# M3_80.net
KiCad netlist of a schematic drawn in EAGLE
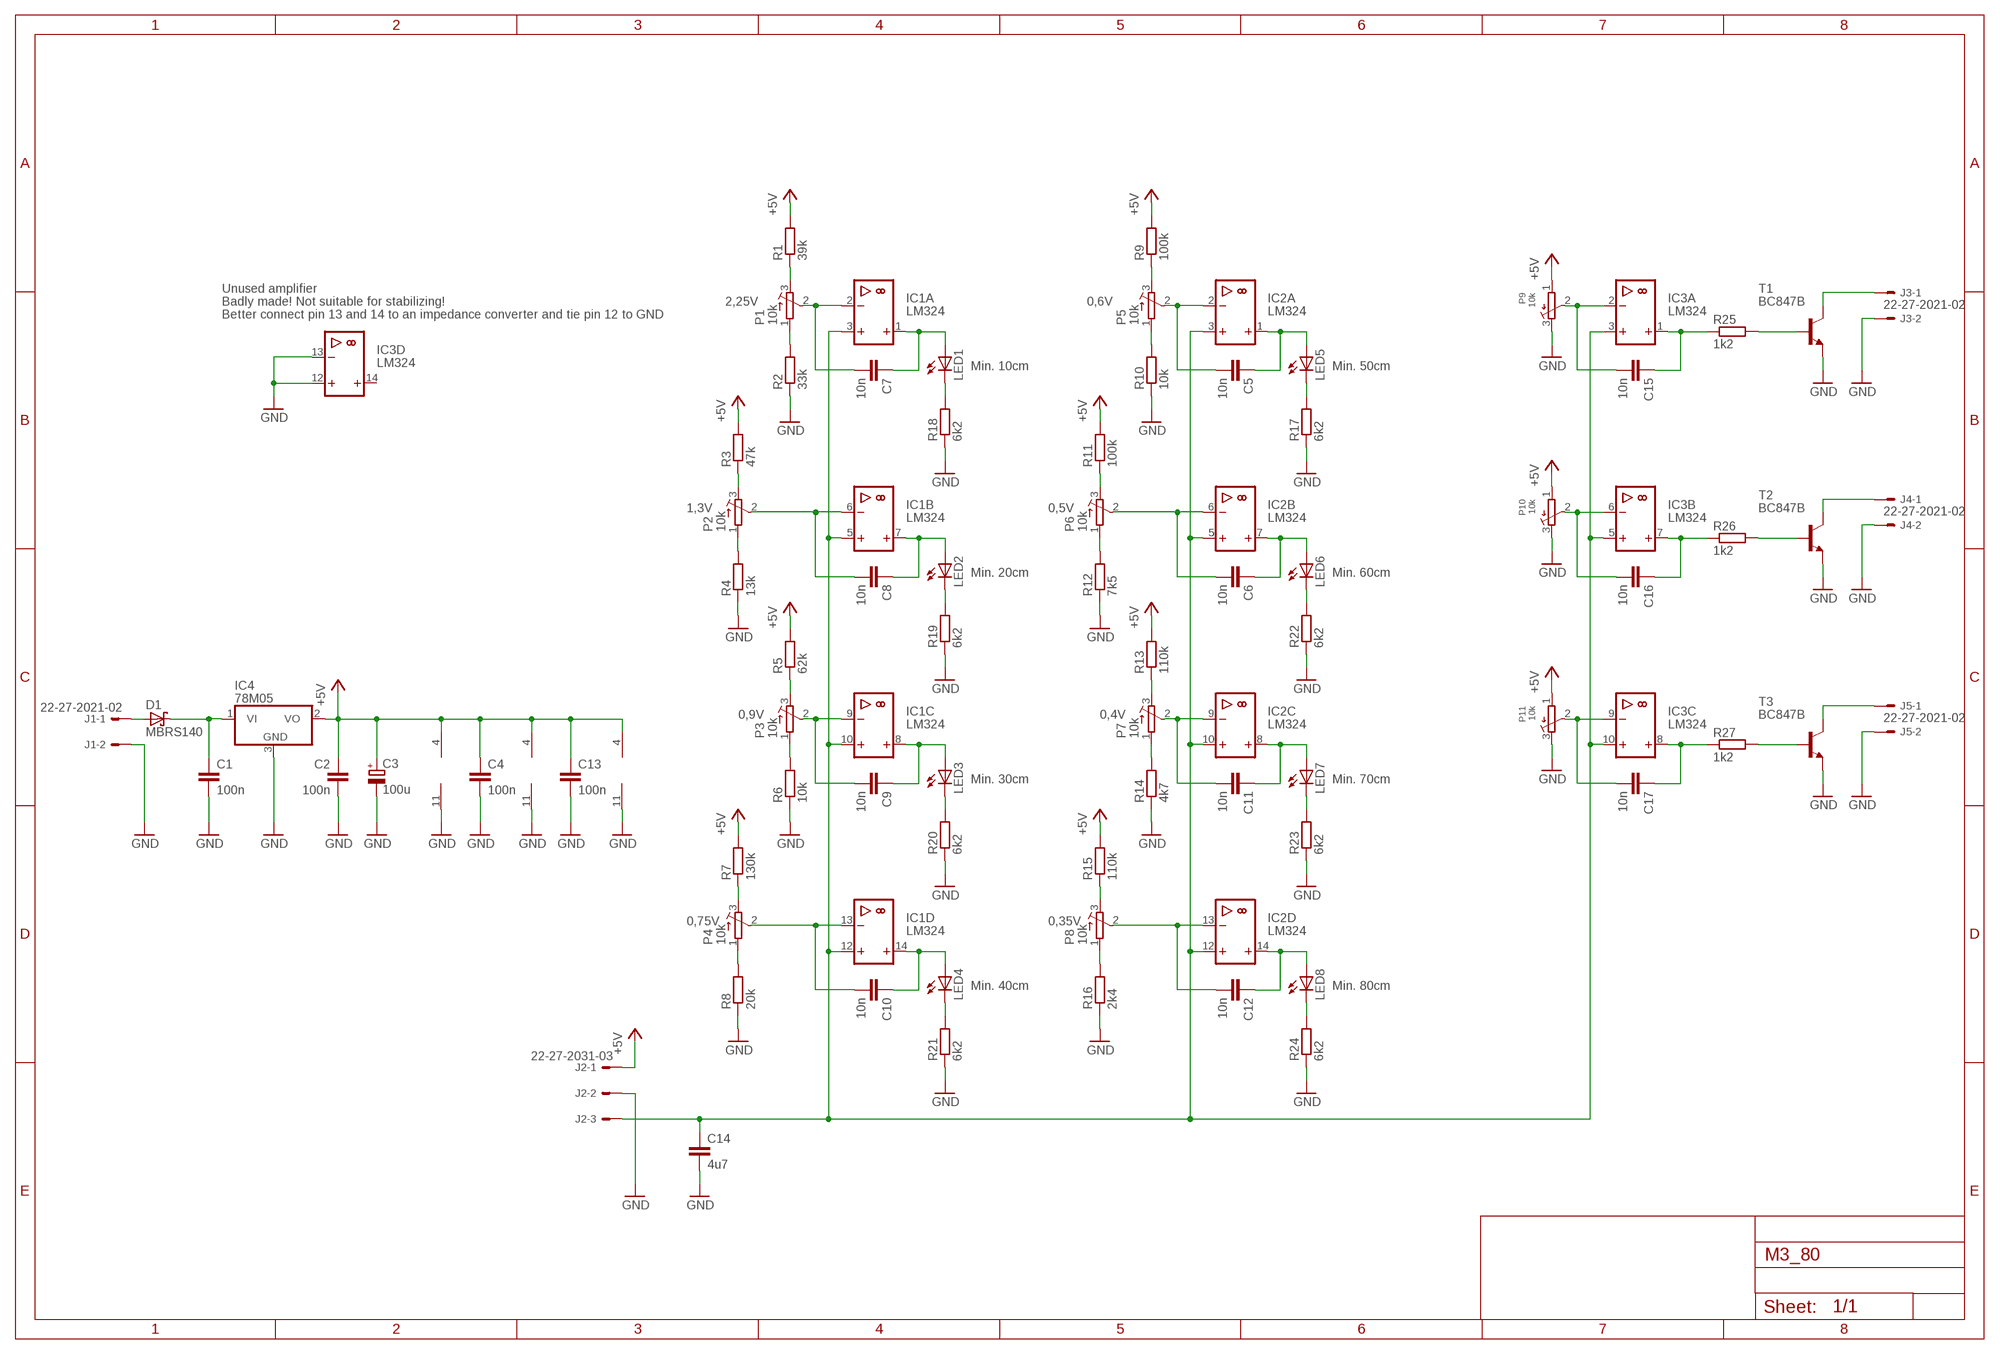
[diagram p0: schematic, sheet 1]

(export (version "E")
  (design (tool "Eeschema 10.0.6"))
  (components
    (comp (ref "C1")
      (value "100n")
      (footprint "eagle-import:C0805K")
      (libsource (lib "eagle-import") (part "C-EUC0805K"))
    )
    (comp (ref "C2")
      (value "100n")
      (footprint "eagle-import:C0805K")
      (libsource (lib "eagle-import") (part "C-EUC0805K"))
    )
    (comp (ref "C3")
      (value "100u")
      (footprint "eagle-import:D_7343-31W")
      (libsource (lib "eagle-import") (part "CPOL-EUD/7343-31W"))
    )
    (comp (ref "C4")
      (value "100n")
      (footprint "eagle-import:C0805K")
      (libsource (lib "eagle-import") (part "C-EUC0805K"))
    )
    (comp (ref "C5")
      (value "10n")
      (footprint "eagle-import:C0805K")
      (libsource (lib "eagle-import") (part "C-EUC0805K"))
    )
    (comp (ref "C6")
      (value "10n")
      (footprint "eagle-import:C0805K")
      (libsource (lib "eagle-import") (part "C-EUC0805K"))
    )
    (comp (ref "C7")
      (value "10n")
      (footprint "eagle-import:C0805K")
      (libsource (lib "eagle-import") (part "C-EUC0805K"))
    )
    (comp (ref "C8")
      (value "10n")
      (footprint "eagle-import:C0805K")
      (libsource (lib "eagle-import") (part "C-EUC0805K"))
    )
    (comp (ref "C9")
      (value "10n")
      (footprint "eagle-import:C0805K")
      (libsource (lib "eagle-import") (part "C-EUC0805K"))
    )
    (comp (ref "C10")
      (value "10n")
      (footprint "eagle-import:C0805K")
      (libsource (lib "eagle-import") (part "C-EUC0805K"))
    )
    (comp (ref "C11")
      (value "10n")
      (footprint "eagle-import:C0805K")
      (libsource (lib "eagle-import") (part "C-EUC0805K"))
    )
    (comp (ref "C12")
      (value "10n")
      (footprint "eagle-import:C0805K")
      (libsource (lib "eagle-import") (part "C-EUC0805K"))
    )
    (comp (ref "C13")
      (value "100n")
      (footprint "eagle-import:C0805K")
      (libsource (lib "eagle-import") (part "C-EUC0805K"))
    )
    (comp (ref "C14")
      (value "4u7")
      (footprint "eagle-import:C0805K")
      (libsource (lib "eagle-import") (part "C-EUC0805K"))
    )
    (comp (ref "C15")
      (value "10n")
      (footprint "eagle-import:C0805K")
      (libsource (lib "eagle-import") (part "C-EUC0805K"))
    )
    (comp (ref "C16")
      (value "10n")
      (footprint "eagle-import:C0805K")
      (libsource (lib "eagle-import") (part "C-EUC0805K"))
    )
    (comp (ref "C17")
      (value "10n")
      (footprint "eagle-import:C0805K")
      (libsource (lib "eagle-import") (part "C-EUC0805K"))
    )
    (comp (ref "D1")
      (value "MBRS140")
      (footprint "eagle-import:SMB")
      (libsource (lib "eagle-import") (part "MBRS130LT3"))
    )
    (comp (ref "IC1")
      (value "LM324")
      (footprint "eagle-import:SO14")
      (libsource (lib "eagle-import") (part "QUAD-OPAMPD"))
    )
    (comp (ref "IC2")
      (value "LM324")
      (footprint "eagle-import:SO14")
      (libsource (lib "eagle-import") (part "QUAD-OPAMPD"))
    )
    (comp (ref "IC3")
      (value "LM324")
      (footprint "eagle-import:SO14")
      (libsource (lib "eagle-import") (part "QUAD-OPAMPD"))
    )
    (comp (ref "IC4")
      (value "78M05")
      (footprint "eagle-import:TO252")
      (libsource (lib "eagle-import") (part "78DT05"))
    )
    (comp (ref "J1")
      (value "22-27-2021-02")
      (footprint "eagle-import:6410-02")
      (libsource (lib "eagle-import") (part "22-?-0227-2021"))
    )
    (comp (ref "J2")
      (value "22-27-2031-03")
      (footprint "eagle-import:6410-03")
      (libsource (lib "eagle-import") (part "22-?-0327-2031"))
    )
    (comp (ref "J3")
      (value "22-27-2021-02")
      (footprint "eagle-import:6410-02")
      (fields (field (name "OC_FARNELL") "unknown") (field (name "OC_NEWARK") "unknown"))
      (libsource (lib "eagle-import") (part "22-?-0227-2021"))
    )
    (comp (ref "J4")
      (value "22-27-2021-02")
      (footprint "eagle-import:6410-02")
      (fields (field (name "OC_FARNELL") "unknown") (field (name "OC_NEWARK") "unknown"))
      (libsource (lib "eagle-import") (part "22-?-0227-2021"))
    )
    (comp (ref "J5")
      (value "22-27-2021-02")
      (footprint "eagle-import:6410-02")
      (fields (field (name "OC_FARNELL") "unknown") (field (name "OC_NEWARK") "unknown"))
      (libsource (lib "eagle-import") (part "22-?-0227-2021"))
    )
    (comp (ref "LED1")
      (value "LED3MM")
      (footprint "eagle-import:LED3MM")
      (libsource (lib "eagle-import") (part "LED3MM"))
    )
    (comp (ref "LED2")
      (value "LED3MM")
      (footprint "eagle-import:LED3MM")
      (libsource (lib "eagle-import") (part "LED3MM"))
    )
    (comp (ref "LED3")
      (value "LED3MM")
      (footprint "eagle-import:LED3MM")
      (libsource (lib "eagle-import") (part "LED3MM"))
    )
    (comp (ref "LED4")
      (value "LED3MM")
      (footprint "eagle-import:LED3MM")
      (libsource (lib "eagle-import") (part "LED3MM"))
    )
    (comp (ref "LED5")
      (value "LED3MM")
      (footprint "eagle-import:LED3MM")
      (libsource (lib "eagle-import") (part "LED3MM"))
    )
    (comp (ref "LED6")
      (value "LED3MM")
      (footprint "eagle-import:LED3MM")
      (libsource (lib "eagle-import") (part "LED3MM"))
    )
    (comp (ref "LED7")
      (value "LED3MM")
      (footprint "eagle-import:LED3MM")
      (libsource (lib "eagle-import") (part "LED3MM"))
    )
    (comp (ref "LED8")
      (value "LED3MM")
      (footprint "eagle-import:LED3MM")
      (libsource (lib "eagle-import") (part "LED3MM"))
    )
    (comp (ref "P1")
      (value "10k")
      (footprint "eagle-import:EVM1D")
      (libsource (lib "eagle-import") (part "EVM1D"))
    )
    (comp (ref "P2")
      (value "10k")
      (footprint "eagle-import:EVM1D")
      (libsource (lib "eagle-import") (part "EVM1D"))
    )
    (comp (ref "P3")
      (value "10k")
      (footprint "eagle-import:EVM1D")
      (libsource (lib "eagle-import") (part "EVM1D"))
    )
    (comp (ref "P4")
      (value "10k")
      (footprint "eagle-import:EVM1D")
      (libsource (lib "eagle-import") (part "EVM1D"))
    )
    (comp (ref "P5")
      (value "10k")
      (footprint "eagle-import:EVM1D")
      (libsource (lib "eagle-import") (part "EVM1D"))
    )
    (comp (ref "P6")
      (value "10k")
      (footprint "eagle-import:EVM1D")
      (libsource (lib "eagle-import") (part "EVM1D"))
    )
    (comp (ref "P7")
      (value "10k")
      (footprint "eagle-import:EVM1D")
      (libsource (lib "eagle-import") (part "EVM1D"))
    )
    (comp (ref "P8")
      (value "10k")
      (footprint "eagle-import:EVM1D")
      (libsource (lib "eagle-import") (part "EVM1D"))
    )
    (comp (ref "P9")
      (value "10k")
      (footprint "eagle-import:T63YA")
      (libsource (lib "eagle-import") (part "T63YA"))
    )
    (comp (ref "P10")
      (value "10k")
      (footprint "eagle-import:T63YA")
      (libsource (lib "eagle-import") (part "T63YA"))
    )
    (comp (ref "P11")
      (value "10k")
      (footprint "eagle-import:T63YA")
      (libsource (lib "eagle-import") (part "T63YA"))
    )
    (comp (ref "R1")
      (value "39k")
      (footprint "eagle-import:M0805")
      (libsource (lib "eagle-import") (part "R-EU_M0805"))
    )
    (comp (ref "R2")
      (value "33k")
      (footprint "eagle-import:M0805")
      (libsource (lib "eagle-import") (part "R-EU_M0805"))
    )
    (comp (ref "R3")
      (value "47k")
      (footprint "eagle-import:M0805")
      (libsource (lib "eagle-import") (part "R-EU_M0805"))
    )
    (comp (ref "R4")
      (value "13k")
      (footprint "eagle-import:M0805")
      (libsource (lib "eagle-import") (part "R-EU_M0805"))
    )
    (comp (ref "R5")
      (value "62k")
      (footprint "eagle-import:M0805")
      (libsource (lib "eagle-import") (part "R-EU_M0805"))
    )
    (comp (ref "R6")
      (value "10k")
      (footprint "eagle-import:M0805")
      (libsource (lib "eagle-import") (part "R-EU_M0805"))
    )
    (comp (ref "R7")
      (value "130k")
      (footprint "eagle-import:M0805")
      (libsource (lib "eagle-import") (part "R-EU_M0805"))
    )
    (comp (ref "R8")
      (value "20k")
      (footprint "eagle-import:M0805")
      (libsource (lib "eagle-import") (part "R-EU_M0805"))
    )
    (comp (ref "R9")
      (value "100k")
      (footprint "eagle-import:M0805")
      (libsource (lib "eagle-import") (part "R-EU_M0805"))
    )
    (comp (ref "R10")
      (value "10k")
      (footprint "eagle-import:M0805")
      (libsource (lib "eagle-import") (part "R-EU_M0805"))
    )
    (comp (ref "R11")
      (value "100k")
      (footprint "eagle-import:M0805")
      (libsource (lib "eagle-import") (part "R-EU_M0805"))
    )
    (comp (ref "R12")
      (value "7k5")
      (footprint "eagle-import:M0805")
      (libsource (lib "eagle-import") (part "R-EU_M0805"))
    )
    (comp (ref "R13")
      (value "110k")
      (footprint "eagle-import:M0805")
      (libsource (lib "eagle-import") (part "R-EU_M0805"))
    )
    (comp (ref "R14")
      (value "4k7")
      (footprint "eagle-import:M0805")
      (libsource (lib "eagle-import") (part "R-EU_M0805"))
    )
    (comp (ref "R15")
      (value "110k")
      (footprint "eagle-import:M0805")
      (libsource (lib "eagle-import") (part "R-EU_M0805"))
    )
    (comp (ref "R16")
      (value "2k4")
      (footprint "eagle-import:M0805")
      (libsource (lib "eagle-import") (part "R-EU_M0805"))
    )
    (comp (ref "R17")
      (value "6k2")
      (footprint "eagle-import:M0805")
      (libsource (lib "eagle-import") (part "R-EU_M0805"))
    )
    (comp (ref "R18")
      (value "6k2")
      (footprint "eagle-import:M0805")
      (libsource (lib "eagle-import") (part "R-EU_M0805"))
    )
    (comp (ref "R19")
      (value "6k2")
      (footprint "eagle-import:M0805")
      (libsource (lib "eagle-import") (part "R-EU_M0805"))
    )
    (comp (ref "R20")
      (value "6k2")
      (footprint "eagle-import:M0805")
      (libsource (lib "eagle-import") (part "R-EU_M0805"))
    )
    (comp (ref "R21")
      (value "6k2")
      (footprint "eagle-import:M0805")
      (libsource (lib "eagle-import") (part "R-EU_M0805"))
    )
    (comp (ref "R22")
      (value "6k2")
      (footprint "eagle-import:M0805")
      (libsource (lib "eagle-import") (part "R-EU_M0805"))
    )
    (comp (ref "R23")
      (value "6k2")
      (footprint "eagle-import:M0805")
      (libsource (lib "eagle-import") (part "R-EU_M0805"))
    )
    (comp (ref "R24")
      (value "6k2")
      (footprint "eagle-import:M0805")
      (libsource (lib "eagle-import") (part "R-EU_M0805"))
    )
    (comp (ref "R25")
      (value "1k2")
      (footprint "eagle-import:M0805")
      (libsource (lib "eagle-import") (part "R-EU_M0805"))
    )
    (comp (ref "R26")
      (value "1k2")
      (footprint "eagle-import:M0805")
      (libsource (lib "eagle-import") (part "R-EU_M0805"))
    )
    (comp (ref "R27")
      (value "1k2")
      (footprint "eagle-import:M0805")
      (libsource (lib "eagle-import") (part "R-EU_M0805"))
    )
    (comp (ref "T1")
      (value "BC847B")
      (footprint "eagle-import:SOT23")
      (libsource (lib "eagle-import") (part "BC847"))
    )
    (comp (ref "T2")
      (value "BC847B")
      (footprint "eagle-import:SOT23")
      (libsource (lib "eagle-import") (part "BC847"))
    )
    (comp (ref "T3")
      (value "BC847B")
      (footprint "eagle-import:SOT23")
      (libsource (lib "eagle-import") (part "BC847"))
    )
  )
  (nets
    (net (code "1") (name "+5V") (class "Default")
      (node (ref "C13") (pin "1") (pinfunction "1_1") (pintype "passive"))
      (node (ref "C2") (pin "1") (pinfunction "1_1") (pintype "passive"))
      (node (ref "C3") (pin "+") (pinfunction "+_+") (pintype "passive"))
      (node (ref "C4") (pin "1") (pinfunction "1_1") (pintype "passive"))
      (node (ref "IC1") (pin "4") (pinfunction "V+_4") (pintype "power_in"))
      (node (ref "IC2") (pin "4") (pinfunction "V+_4") (pintype "power_in"))
      (node (ref "IC3") (pin "4") (pinfunction "V+_4") (pintype "power_in"))
      (node (ref "IC4") (pin "2") (pinfunction "VO_2") (pintype "passive"))
      (node (ref "J2") (pin "1") (pinfunction "S_1") (pintype "passive"))
      (node (ref "P10") (pin "1") (pinfunction "P$1_1") (pintype "bidirectional"))
      (node (ref "P11") (pin "1") (pinfunction "P$1_1") (pintype "bidirectional"))
      (node (ref "P9") (pin "1") (pinfunction "P$1_1") (pintype "bidirectional"))
      (node (ref "R1") (pin "2") (pinfunction "2_2") (pintype "passive"))
      (node (ref "R11") (pin "2") (pinfunction "2_2") (pintype "passive"))
      (node (ref "R13") (pin "2") (pinfunction "2_2") (pintype "passive"))
      (node (ref "R15") (pin "2") (pinfunction "2_2") (pintype "passive"))
      (node (ref "R3") (pin "2") (pinfunction "2_2") (pintype "passive"))
      (node (ref "R5") (pin "2") (pinfunction "2_2") (pintype "passive"))
      (node (ref "R7") (pin "2") (pinfunction "2_2") (pintype "passive"))
      (node (ref "R9") (pin "2") (pinfunction "2_2") (pintype "passive"))
    )
    (net (code "2") (name "GND") (class "Default")
      (node (ref "C1") (pin "2") (pinfunction "2_2") (pintype "passive"))
      (node (ref "C13") (pin "2") (pinfunction "2_2") (pintype "passive"))
      (node (ref "C14") (pin "2") (pinfunction "2_2") (pintype "passive"))
      (node (ref "C2") (pin "2") (pinfunction "2_2") (pintype "passive"))
      (node (ref "C3") (pin "-") (pinfunction "-_-") (pintype "passive"))
      (node (ref "C4") (pin "2") (pinfunction "2_2") (pintype "passive"))
      (node (ref "IC1") (pin "11") (pinfunction "V-_11") (pintype "power_in"))
      (node (ref "IC2") (pin "11") (pinfunction "V-_11") (pintype "power_in"))
      (node (ref "IC3") (pin "11") (pinfunction "V-_11") (pintype "power_in"))
      (node (ref "IC3") (pin "12") (pinfunction "+IN_12") (pintype "input"))
      (node (ref "IC3") (pin "13") (pinfunction "-IN_13") (pintype "input"))
      (node (ref "IC4") (pin "3") (pinfunction "GND_3") (pintype "passive"))
      (node (ref "J1") (pin "2") (pinfunction "S_2") (pintype "passive"))
      (node (ref "J2") (pin "2") (pinfunction "S_2") (pintype "passive"))
      (node (ref "J3") (pin "2") (pinfunction "S_2") (pintype "passive"))
      (node (ref "J4") (pin "2") (pinfunction "S_2") (pintype "passive"))
      (node (ref "J5") (pin "2") (pinfunction "S_2") (pintype "passive"))
      (node (ref "P10") (pin "3") (pinfunction "P$3_3") (pintype "bidirectional"))
      (node (ref "P11") (pin "3") (pinfunction "P$3_3") (pintype "bidirectional"))
      (node (ref "P9") (pin "3") (pinfunction "P$3_3") (pintype "bidirectional"))
      (node (ref "R10") (pin "1") (pinfunction "1_1") (pintype "passive"))
      (node (ref "R12") (pin "1") (pinfunction "1_1") (pintype "passive"))
      (node (ref "R14") (pin "1") (pinfunction "1_1") (pintype "passive"))
      (node (ref "R16") (pin "1") (pinfunction "1_1") (pintype "passive"))
      (node (ref "R17") (pin "1") (pinfunction "1_1") (pintype "passive"))
      (node (ref "R18") (pin "1") (pinfunction "1_1") (pintype "passive"))
      (node (ref "R19") (pin "1") (pinfunction "1_1") (pintype "passive"))
      (node (ref "R2") (pin "1") (pinfunction "1_1") (pintype "passive"))
      (node (ref "R20") (pin "1") (pinfunction "1_1") (pintype "passive"))
      (node (ref "R21") (pin "1") (pinfunction "1_1") (pintype "passive"))
      (node (ref "R22") (pin "1") (pinfunction "1_1") (pintype "passive"))
      (node (ref "R23") (pin "1") (pinfunction "1_1") (pintype "passive"))
      (node (ref "R24") (pin "1") (pinfunction "1_1") (pintype "passive"))
      (node (ref "R4") (pin "1") (pinfunction "1_1") (pintype "passive"))
      (node (ref "R6") (pin "1") (pinfunction "1_1") (pintype "passive"))
      (node (ref "R8") (pin "1") (pinfunction "1_1") (pintype "passive"))
      (node (ref "T1") (pin "2") (pinfunction "E_2") (pintype "passive"))
      (node (ref "T2") (pin "2") (pinfunction "E_2") (pintype "passive"))
      (node (ref "T3") (pin "2") (pinfunction "E_2") (pintype "passive"))
    )
    (net (code "3") (name "Net-(IC1A-+IN)") (class "Default")
      (node (ref "C14") (pin "1") (pinfunction "1_1") (pintype "passive"))
      (node (ref "IC1") (pin "10") (pinfunction "+IN_10") (pintype "input"))
      (node (ref "IC1") (pin "12") (pinfunction "+IN_12") (pintype "input"))
      (node (ref "IC1") (pin "3") (pinfunction "+IN_3") (pintype "input"))
      (node (ref "IC1") (pin "5") (pinfunction "+IN_5") (pintype "input"))
      (node (ref "IC2") (pin "10") (pinfunction "+IN_10") (pintype "input"))
      (node (ref "IC2") (pin "12") (pinfunction "+IN_12") (pintype "input"))
      (node (ref "IC2") (pin "3") (pinfunction "+IN_3") (pintype "input"))
      (node (ref "IC2") (pin "5") (pinfunction "+IN_5") (pintype "input"))
      (node (ref "IC3") (pin "10") (pinfunction "+IN_10") (pintype "input"))
      (node (ref "IC3") (pin "3") (pinfunction "+IN_3") (pintype "input"))
      (node (ref "IC3") (pin "5") (pinfunction "+IN_5") (pintype "input"))
      (node (ref "J2") (pin "3") (pinfunction "S_3") (pintype "passive"))
    )
    (net (code "4") (name "Net-(IC1A--IN)") (class "Default")
      (node (ref "C7") (pin "2") (pinfunction "2_2") (pintype "passive"))
      (node (ref "IC1") (pin "2") (pinfunction "-IN_2") (pintype "input"))
      (node (ref "P1") (pin "2") (pinfunction "P$2_2") (pintype "bidirectional"))
    )
    (net (code "5") (name "Net-(IC1A-OUT)") (class "Default")
      (node (ref "C7") (pin "1") (pinfunction "1_1") (pintype "passive"))
      (node (ref "IC1") (pin "1") (pinfunction "OUT_1") (pintype "output"))
      (node (ref "LED1") (pin "A") (pinfunction "A_A") (pintype "passive"))
    )
    (net (code "6") (name "Net-(IC1B--IN)") (class "Default")
      (node (ref "C8") (pin "2") (pinfunction "2_2") (pintype "passive"))
      (node (ref "IC1") (pin "6") (pinfunction "-IN_6") (pintype "input"))
      (node (ref "P2") (pin "2") (pinfunction "P$2_2") (pintype "bidirectional"))
    )
    (net (code "7") (name "Net-(IC1B-OUT)") (class "Default")
      (node (ref "C8") (pin "1") (pinfunction "1_1") (pintype "passive"))
      (node (ref "IC1") (pin "7") (pinfunction "OUT_7") (pintype "output"))
      (node (ref "LED2") (pin "A") (pinfunction "A_A") (pintype "passive"))
    )
    (net (code "8") (name "Net-(IC1C--IN)") (class "Default")
      (node (ref "C9") (pin "2") (pinfunction "2_2") (pintype "passive"))
      (node (ref "IC1") (pin "9") (pinfunction "-IN_9") (pintype "input"))
      (node (ref "P3") (pin "2") (pinfunction "P$2_2") (pintype "bidirectional"))
    )
    (net (code "9") (name "Net-(IC1C-OUT)") (class "Default")
      (node (ref "C9") (pin "1") (pinfunction "1_1") (pintype "passive"))
      (node (ref "IC1") (pin "8") (pinfunction "OUT_8") (pintype "output"))
      (node (ref "LED3") (pin "A") (pinfunction "A_A") (pintype "passive"))
    )
    (net (code "10") (name "Net-(IC1D--IN)") (class "Default")
      (node (ref "C10") (pin "2") (pinfunction "2_2") (pintype "passive"))
      (node (ref "IC1") (pin "13") (pinfunction "-IN_13") (pintype "input"))
      (node (ref "P4") (pin "2") (pinfunction "P$2_2") (pintype "bidirectional"))
    )
    (net (code "11") (name "Net-(IC1D-OUT)") (class "Default")
      (node (ref "C10") (pin "1") (pinfunction "1_1") (pintype "passive"))
      (node (ref "IC1") (pin "14") (pinfunction "OUT_14") (pintype "output"))
      (node (ref "LED4") (pin "A") (pinfunction "A_A") (pintype "passive"))
    )
    (net (code "12") (name "Net-(IC2A--IN)") (class "Default")
      (node (ref "C5") (pin "2") (pinfunction "2_2") (pintype "passive"))
      (node (ref "IC2") (pin "2") (pinfunction "-IN_2") (pintype "input"))
      (node (ref "P5") (pin "2") (pinfunction "P$2_2") (pintype "bidirectional"))
    )
    (net (code "13") (name "Net-(IC2A-OUT)") (class "Default")
      (node (ref "C5") (pin "1") (pinfunction "1_1") (pintype "passive"))
      (node (ref "IC2") (pin "1") (pinfunction "OUT_1") (pintype "output"))
      (node (ref "LED5") (pin "A") (pinfunction "A_A") (pintype "passive"))
    )
    (net (code "14") (name "Net-(IC2B--IN)") (class "Default")
      (node (ref "C6") (pin "2") (pinfunction "2_2") (pintype "passive"))
      (node (ref "IC2") (pin "6") (pinfunction "-IN_6") (pintype "input"))
      (node (ref "P6") (pin "2") (pinfunction "P$2_2") (pintype "bidirectional"))
    )
    (net (code "15") (name "Net-(IC2B-OUT)") (class "Default")
      (node (ref "C6") (pin "1") (pinfunction "1_1") (pintype "passive"))
      (node (ref "IC2") (pin "7") (pinfunction "OUT_7") (pintype "output"))
      (node (ref "LED6") (pin "A") (pinfunction "A_A") (pintype "passive"))
    )
    (net (code "16") (name "Net-(IC2C--IN)") (class "Default")
      (node (ref "C11") (pin "2") (pinfunction "2_2") (pintype "passive"))
      (node (ref "IC2") (pin "9") (pinfunction "-IN_9") (pintype "input"))
      (node (ref "P7") (pin "2") (pinfunction "P$2_2") (pintype "bidirectional"))
    )
    (net (code "17") (name "Net-(IC2C-OUT)") (class "Default")
      (node (ref "C11") (pin "1") (pinfunction "1_1") (pintype "passive"))
      (node (ref "IC2") (pin "8") (pinfunction "OUT_8") (pintype "output"))
      (node (ref "LED7") (pin "A") (pinfunction "A_A") (pintype "passive"))
    )
    (net (code "18") (name "Net-(IC2D--IN)") (class "Default")
      (node (ref "C12") (pin "2") (pinfunction "2_2") (pintype "passive"))
      (node (ref "IC2") (pin "13") (pinfunction "-IN_13") (pintype "input"))
      (node (ref "P8") (pin "2") (pinfunction "P$2_2") (pintype "bidirectional"))
    )
    (net (code "19") (name "Net-(IC2D-OUT)") (class "Default")
      (node (ref "C12") (pin "1") (pinfunction "1_1") (pintype "passive"))
      (node (ref "IC2") (pin "14") (pinfunction "OUT_14") (pintype "output"))
      (node (ref "LED8") (pin "A") (pinfunction "A_A") (pintype "passive"))
    )
    (net (code "20") (name "Net-(IC3A--IN)") (class "Default")
      (node (ref "C15") (pin "2") (pinfunction "2_2") (pintype "passive"))
      (node (ref "IC3") (pin "2") (pinfunction "-IN_2") (pintype "input"))
      (node (ref "P9") (pin "2") (pinfunction "P$2_2") (pintype "bidirectional"))
    )
    (net (code "21") (name "Net-(IC3A-OUT)") (class "Default")
      (node (ref "C15") (pin "1") (pinfunction "1_1") (pintype "passive"))
      (node (ref "IC3") (pin "1") (pinfunction "OUT_1") (pintype "output"))
      (node (ref "R25") (pin "1") (pinfunction "1_1") (pintype "passive"))
    )
    (net (code "22") (name "Net-(IC3B--IN)") (class "Default")
      (node (ref "C16") (pin "2") (pinfunction "2_2") (pintype "passive"))
      (node (ref "IC3") (pin "6") (pinfunction "-IN_6") (pintype "input"))
      (node (ref "P10") (pin "2") (pinfunction "P$2_2") (pintype "bidirectional"))
    )
    (net (code "23") (name "Net-(IC3B-OUT)") (class "Default")
      (node (ref "C16") (pin "1") (pinfunction "1_1") (pintype "passive"))
      (node (ref "IC3") (pin "7") (pinfunction "OUT_7") (pintype "output"))
      (node (ref "R26") (pin "1") (pinfunction "1_1") (pintype "passive"))
    )
    (net (code "24") (name "Net-(IC3C--IN)") (class "Default")
      (node (ref "C17") (pin "2") (pinfunction "2_2") (pintype "passive"))
      (node (ref "IC3") (pin "9") (pinfunction "-IN_9") (pintype "input"))
      (node (ref "P11") (pin "2") (pinfunction "P$2_2") (pintype "bidirectional"))
    )
    (net (code "25") (name "Net-(IC3C-OUT)") (class "Default")
      (node (ref "C17") (pin "1") (pinfunction "1_1") (pintype "passive"))
      (node (ref "IC3") (pin "8") (pinfunction "OUT_8") (pintype "output"))
      (node (ref "R27") (pin "1") (pinfunction "1_1") (pintype "passive"))
    )
    (net (code "26") (name "Net-(IC4-VI)") (class "Default")
      (node (ref "C1") (pin "1") (pinfunction "1_1") (pintype "passive"))
      (node (ref "D1") (pin "C") (pinfunction "C_C") (pintype "passive"))
      (node (ref "IC4") (pin "1") (pinfunction "VI_1") (pintype "input"))
    )
    (net (code "27") (name "Net-(J1A-S)") (class "Default")
      (node (ref "D1") (pin "A") (pinfunction "A_A") (pintype "passive"))
      (node (ref "J1") (pin "1") (pinfunction "S_1") (pintype "passive"))
    )
    (net (code "28") (name "Net-(J3A-S)") (class "Default")
      (node (ref "J3") (pin "1") (pinfunction "S_1") (pintype "passive"))
      (node (ref "T1") (pin "3") (pinfunction "C_3") (pintype "passive"))
    )
    (net (code "29") (name "Net-(J4A-S)") (class "Default")
      (node (ref "J4") (pin "1") (pinfunction "S_1") (pintype "passive"))
      (node (ref "T2") (pin "3") (pinfunction "C_3") (pintype "passive"))
    )
    (net (code "30") (name "Net-(J5A-S)") (class "Default")
      (node (ref "J5") (pin "1") (pinfunction "S_1") (pintype "passive"))
      (node (ref "T3") (pin "3") (pinfunction "C_3") (pintype "passive"))
    )
    (net (code "31") (name "Net-(LED1-C)") (class "Default")
      (node (ref "LED1") (pin "K") (pinfunction "C_K") (pintype "passive"))
      (node (ref "R18") (pin "2") (pinfunction "2_2") (pintype "passive"))
    )
    (net (code "32") (name "Net-(LED2-C)") (class "Default")
      (node (ref "LED2") (pin "K") (pinfunction "C_K") (pintype "passive"))
      (node (ref "R19") (pin "2") (pinfunction "2_2") (pintype "passive"))
    )
    (net (code "33") (name "Net-(LED3-C)") (class "Default")
      (node (ref "LED3") (pin "K") (pinfunction "C_K") (pintype "passive"))
      (node (ref "R20") (pin "2") (pinfunction "2_2") (pintype "passive"))
    )
    (net (code "34") (name "Net-(LED4-C)") (class "Default")
      (node (ref "LED4") (pin "K") (pinfunction "C_K") (pintype "passive"))
      (node (ref "R21") (pin "2") (pinfunction "2_2") (pintype "passive"))
    )
    (net (code "35") (name "Net-(LED5-C)") (class "Default")
      (node (ref "LED5") (pin "K") (pinfunction "C_K") (pintype "passive"))
      (node (ref "R17") (pin "2") (pinfunction "2_2") (pintype "passive"))
    )
    (net (code "36") (name "Net-(LED6-C)") (class "Default")
      (node (ref "LED6") (pin "K") (pinfunction "C_K") (pintype "passive"))
      (node (ref "R22") (pin "2") (pinfunction "2_2") (pintype "passive"))
    )
    (net (code "37") (name "Net-(LED7-C)") (class "Default")
      (node (ref "LED7") (pin "K") (pinfunction "C_K") (pintype "passive"))
      (node (ref "R23") (pin "2") (pinfunction "2_2") (pintype "passive"))
    )
    (net (code "38") (name "Net-(LED8-C)") (class "Default")
      (node (ref "LED8") (pin "K") (pinfunction "C_K") (pintype "passive"))
      (node (ref "R24") (pin "2") (pinfunction "2_2") (pintype "passive"))
    )
    (net (code "39") (name "Net-(P1-P$1)") (class "Default")
      (node (ref "P1") (pin "1") (pinfunction "P$1_1") (pintype "bidirectional"))
      (node (ref "R2") (pin "2") (pinfunction "2_2") (pintype "passive"))
    )
    (net (code "40") (name "Net-(P1-P$3)") (class "Default")
      (node (ref "P1") (pin "3") (pinfunction "P$3_3") (pintype "bidirectional"))
      (node (ref "R1") (pin "1") (pinfunction "1_1") (pintype "passive"))
    )
    (net (code "41") (name "Net-(P2-P$1)") (class "Default")
      (node (ref "P2") (pin "1") (pinfunction "P$1_1") (pintype "bidirectional"))
      (node (ref "R4") (pin "2") (pinfunction "2_2") (pintype "passive"))
    )
    (net (code "42") (name "Net-(P2-P$3)") (class "Default")
      (node (ref "P2") (pin "3") (pinfunction "P$3_3") (pintype "bidirectional"))
      (node (ref "R3") (pin "1") (pinfunction "1_1") (pintype "passive"))
    )
    (net (code "43") (name "Net-(P3-P$1)") (class "Default")
      (node (ref "P3") (pin "1") (pinfunction "P$1_1") (pintype "bidirectional"))
      (node (ref "R6") (pin "2") (pinfunction "2_2") (pintype "passive"))
    )
    (net (code "44") (name "Net-(P3-P$3)") (class "Default")
      (node (ref "P3") (pin "3") (pinfunction "P$3_3") (pintype "bidirectional"))
      (node (ref "R5") (pin "1") (pinfunction "1_1") (pintype "passive"))
    )
    (net (code "45") (name "Net-(P4-P$1)") (class "Default")
      (node (ref "P4") (pin "1") (pinfunction "P$1_1") (pintype "bidirectional"))
      (node (ref "R8") (pin "2") (pinfunction "2_2") (pintype "passive"))
    )
    (net (code "46") (name "Net-(P4-P$3)") (class "Default")
      (node (ref "P4") (pin "3") (pinfunction "P$3_3") (pintype "bidirectional"))
      (node (ref "R7") (pin "1") (pinfunction "1_1") (pintype "passive"))
    )
    (net (code "47") (name "Net-(P5-P$1)") (class "Default")
      (node (ref "P5") (pin "1") (pinfunction "P$1_1") (pintype "bidirectional"))
      (node (ref "R10") (pin "2") (pinfunction "2_2") (pintype "passive"))
    )
    (net (code "48") (name "Net-(P5-P$3)") (class "Default")
      (node (ref "P5") (pin "3") (pinfunction "P$3_3") (pintype "bidirectional"))
      (node (ref "R9") (pin "1") (pinfunction "1_1") (pintype "passive"))
    )
    (net (code "49") (name "Net-(P6-P$1)") (class "Default")
      (node (ref "P6") (pin "1") (pinfunction "P$1_1") (pintype "bidirectional"))
      (node (ref "R12") (pin "2") (pinfunction "2_2") (pintype "passive"))
    )
    (net (code "50") (name "Net-(P6-P$3)") (class "Default")
      (node (ref "P6") (pin "3") (pinfunction "P$3_3") (pintype "bidirectional"))
      (node (ref "R11") (pin "1") (pinfunction "1_1") (pintype "passive"))
    )
    (net (code "51") (name "Net-(P7-P$1)") (class "Default")
      (node (ref "P7") (pin "1") (pinfunction "P$1_1") (pintype "bidirectional"))
      (node (ref "R14") (pin "2") (pinfunction "2_2") (pintype "passive"))
    )
    (net (code "52") (name "Net-(P7-P$3)") (class "Default")
      (node (ref "P7") (pin "3") (pinfunction "P$3_3") (pintype "bidirectional"))
      (node (ref "R13") (pin "1") (pinfunction "1_1") (pintype "passive"))
    )
    (net (code "53") (name "Net-(P8-P$1)") (class "Default")
      (node (ref "P8") (pin "1") (pinfunction "P$1_1") (pintype "bidirectional"))
      (node (ref "R16") (pin "2") (pinfunction "2_2") (pintype "passive"))
    )
    (net (code "54") (name "Net-(P8-P$3)") (class "Default")
      (node (ref "P8") (pin "3") (pinfunction "P$3_3") (pintype "bidirectional"))
      (node (ref "R15") (pin "1") (pinfunction "1_1") (pintype "passive"))
    )
    (net (code "55") (name "Net-(T1-B)") (class "Default")
      (node (ref "R25") (pin "2") (pinfunction "2_2") (pintype "passive"))
      (node (ref "T1") (pin "1") (pinfunction "B_1") (pintype "passive"))
    )
    (net (code "56") (name "Net-(T2-B)") (class "Default")
      (node (ref "R26") (pin "2") (pinfunction "2_2") (pintype "passive"))
      (node (ref "T2") (pin "1") (pinfunction "B_1") (pintype "passive"))
    )
    (net (code "57") (name "Net-(T3-B)") (class "Default")
      (node (ref "R27") (pin "2") (pinfunction "2_2") (pintype "passive"))
      (node (ref "T3") (pin "1") (pinfunction "B_1") (pintype "passive"))
    )
    (net (code "58") (name "unconnected-(IC3D-OUT-Pad14)") (class "Default")
      (node (ref "IC3") (pin "14") (pinfunction "OUT_14") (pintype "output"))
    )
  )
)
